# filter.net
KiCad netlist of a schematic drawn in EAGLE
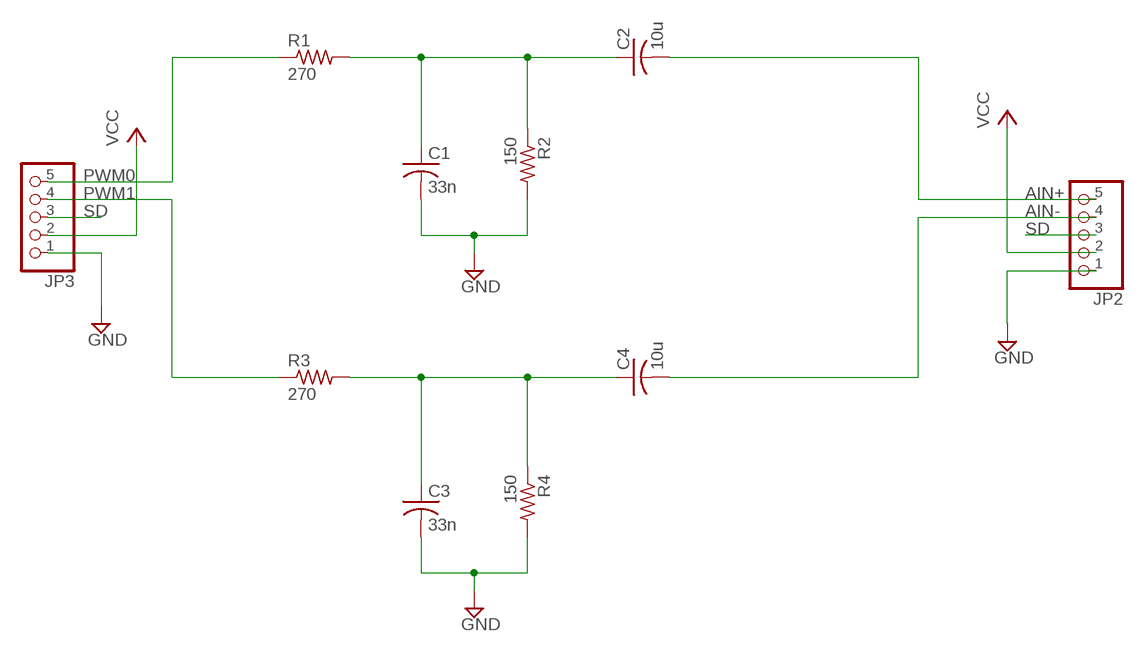
[diagram p0: schematic, sheet 1]

(export (version "E")
  (design (tool "Eeschema 10.0.6"))
  (components
    (comp (ref "C1")
      (value "33n")
      (footprint "eagle-import:C0805")
      (libsource (lib "eagle-import") (part "C-USC0805"))
    )
    (comp (ref "C2")
      (value "10u")
      (footprint "eagle-import:C0805")
      (libsource (lib "eagle-import") (part "C-USC0805"))
    )
    (comp (ref "C3")
      (value "33n")
      (footprint "eagle-import:C0805")
      (libsource (lib "eagle-import") (part "C-USC0805"))
    )
    (comp (ref "C4")
      (value "10u")
      (footprint "eagle-import:C0805")
      (libsource (lib "eagle-import") (part "C-USC0805"))
    )
    (comp (ref "JP2")
      (value "PINHD-1X5")
      (footprint "eagle-import:1X05")
      (libsource (lib "eagle-import") (part "PINHD-1X5"))
    )
    (comp (ref "JP3")
      (value "PINHD-1X5")
      (footprint "eagle-import:1X05")
      (libsource (lib "eagle-import") (part "PINHD-1X5"))
    )
    (comp (ref "R1")
      (value "270")
      (footprint "eagle-import:M0805")
      (libsource (lib "eagle-import") (part "R-US_M0805"))
    )
    (comp (ref "R2")
      (value "150")
      (footprint "eagle-import:M0805")
      (libsource (lib "eagle-import") (part "R-US_M0805"))
    )
    (comp (ref "R3")
      (value "270")
      (footprint "eagle-import:M0805")
      (libsource (lib "eagle-import") (part "R-US_M0805"))
    )
    (comp (ref "R4")
      (value "150")
      (footprint "eagle-import:M0805")
      (libsource (lib "eagle-import") (part "R-US_M0805"))
    )
  )
  (nets
    (net (code "1") (name "/AIN+") (class "Default")
      (node (ref "C2") (pin "2") (pinfunction "2_2") (pintype "passive"))
      (node (ref "JP2") (pin "5") (pinfunction "5_5") (pintype "passive"))
    )
    (net (code "2") (name "/AIN-") (class "Default")
      (node (ref "C4") (pin "2") (pinfunction "2_2") (pintype "passive"))
      (node (ref "JP2") (pin "4") (pinfunction "4_4") (pintype "passive"))
    )
    (net (code "3") (name "/PWM0") (class "Default")
      (node (ref "JP3") (pin "5") (pinfunction "5_5") (pintype "passive"))
      (node (ref "R1") (pin "1") (pinfunction "1_1") (pintype "passive"))
    )
    (net (code "4") (name "/PWM1") (class "Default")
      (node (ref "JP3") (pin "4") (pinfunction "4_4") (pintype "passive"))
      (node (ref "R3") (pin "1") (pinfunction "1_1") (pintype "passive"))
    )
    (net (code "5") (name "/SD") (class "Default")
      (node (ref "JP2") (pin "3") (pinfunction "3_3") (pintype "passive"))
      (node (ref "JP3") (pin "3") (pinfunction "3_3") (pintype "passive"))
    )
    (net (code "6") (name "GND") (class "Default")
      (node (ref "C1") (pin "2") (pinfunction "2_2") (pintype "passive"))
      (node (ref "C3") (pin "2") (pinfunction "2_2") (pintype "passive"))
      (node (ref "JP2") (pin "1") (pinfunction "1_1") (pintype "passive"))
      (node (ref "JP3") (pin "1") (pinfunction "1_1") (pintype "passive"))
      (node (ref "R2") (pin "2") (pinfunction "2_2") (pintype "passive"))
      (node (ref "R4") (pin "2") (pinfunction "2_2") (pintype "passive"))
    )
    (net (code "7") (name "Net-(C1-Pad1)") (class "Default")
      (node (ref "C1") (pin "1") (pinfunction "1_1") (pintype "passive"))
      (node (ref "C2") (pin "1") (pinfunction "1_1") (pintype "passive"))
      (node (ref "R1") (pin "2") (pinfunction "2_2") (pintype "passive"))
      (node (ref "R2") (pin "1") (pinfunction "1_1") (pintype "passive"))
    )
    (net (code "8") (name "Net-(C3-Pad1)") (class "Default")
      (node (ref "C3") (pin "1") (pinfunction "1_1") (pintype "passive"))
      (node (ref "C4") (pin "1") (pinfunction "1_1") (pintype "passive"))
      (node (ref "R3") (pin "2") (pinfunction "2_2") (pintype "passive"))
      (node (ref "R4") (pin "1") (pinfunction "1_1") (pintype "passive"))
    )
    (net (code "9") (name "VCC") (class "Default")
      (node (ref "JP2") (pin "2") (pinfunction "2_2") (pintype "passive"))
      (node (ref "JP3") (pin "2") (pinfunction "2_2") (pintype "passive"))
    )
  )
)
